# Mic_SPK2.net
KiCad netlist of a schematic drawn in Altium Designer
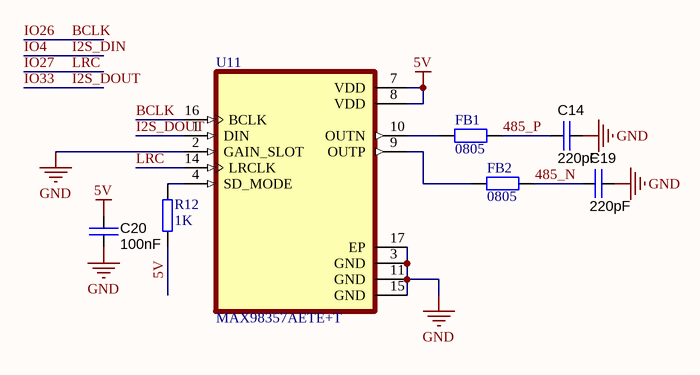
[diagram p0: Mic_SPK2.SchDoc]

(export (version "E")
  (design (tool "Eeschema 10.0.6"))
  (components
    (comp (ref "C14")
      (value "220pF")
      (footprint "CAPC1608X90N")
      (description "Capacitor SMD Cer 470nF 10% 16V X7R 0603")
      (fields (field (name "TOLERANCE") "±10%"))
      (libsource (lib "My library altium") (part "CAP C_0603"))
    )
    (comp (ref "C19")
      (value "220pF")
      (footprint "CAPC1608X90N")
      (description "Capacitor SMD Cer 470nF 10% 16V X7R 0603")
      (fields (field (name "TOLERANCE") "±10%"))
      (libsource (lib "My library altium") (part "CAP C_0603"))
    )
    (comp (ref "C20")
      (value "100nF")
      (footprint "CAPC1608X90N")
      (description "Capacitor SMD Cer 470nF 10% 16V X7R 0603")
      (fields (field (name "TOLERANCE") "±10%"))
      (libsource (lib "My library altium") (part "CAP C_0603"))
    )
    (comp (ref "FB1")
      (value "0805")
      (footprint "DIEN TRO 0805")
      (description "Resistor SMD 0805")
      (fields (field (name "Comment") "R0805") (field (name "PUBLISHER") "Altium Limited"))
      (libsource (lib "My Library") (part "R0805"))
    )
    (comp (ref "FB2")
      (value "0805")
      (footprint "DIEN TRO 0805")
      (description "Resistor SMD 0805")
      (fields (field (name "Comment") "R0805") (field (name "PUBLISHER") "Altium Limited"))
      (libsource (lib "My Library") (part "R0805"))
    )
    (comp (ref "R12")
      (value "1K")
      (footprint "SMT0603")
      (description "RES SM 0603 1K")
      (fields (field (name "Comment") "Resistor"))
      (libsource (lib "electronpowered") (part "RES-SM-0603-1K"))
    )
    (comp (ref "U11")
      (value "MAX98357AETE+T")
      (footprint "QFN50P300X300X80-17N")
      (description "Amplifier IC 1-Channel _Mono_ Class D 16-TQFN _3x3_")
      (fields (field (name "MF") "Maxim Integrated"))
      (libsource (lib "MAX98357AETE_T") (part "MAX98357AETE+T"))
    )
  )
  (nets
    (net (code "1") (name "/485_N") (class "Default")
      (node (ref "C19") (pin "1") (pintype "passive"))
      (node (ref "FB2") (pin "2") (pinfunction "2_2") (pintype "passive"))
    )
    (net (code "2") (name "/485_P") (class "Default")
      (node (ref "C14") (pin "1") (pintype "passive"))
      (node (ref "FB1") (pin "2") (pinfunction "2_2") (pintype "passive"))
    )
    (net (code "3") (name "/BCLK") (class "Default")
      (node (ref "U11") (pin "16") (pinfunction "BCLK_16") (pintype "input"))
    )
    (net (code "5") (name "/I2S_DOUT") (class "Default")
      (node (ref "U11") (pin "1") (pinfunction "DIN_1") (pintype "input"))
    )
    (net (code "6") (name "/IO27") (class "Default")
      (node (ref "U11") (pin "14") (pinfunction "LRCLK_14") (pintype "input"))
    )
    (net (code "7") (name "5V") (class "Default")
      (node (ref "C20") (pin "1") (pintype "passive"))
      (node (ref "R12") (pin "1") (pinfunction "1_1") (pintype "passive"))
      (node (ref "U11") (pin "7") (pinfunction "VDD_7") (pintype "power_in"))
      (node (ref "U11") (pin "8") (pinfunction "VDD_8") (pintype "power_in"))
    )
    (net (code "8") (name "GND") (class "Default")
      (node (ref "C14") (pin "2") (pintype "passive"))
      (node (ref "C19") (pin "2") (pintype "passive"))
      (node (ref "C20") (pin "2") (pintype "passive"))
      (node (ref "U11") (pin "11") (pinfunction "GND_11") (pintype "power_in"))
      (node (ref "U11") (pin "15") (pinfunction "GND_15") (pintype "power_in"))
      (node (ref "U11") (pin "17") (pinfunction "EP_17") (pintype "power_in"))
      (node (ref "U11") (pin "2") (pinfunction "GAIN_SLOT_2") (pintype "input"))
      (node (ref "U11") (pin "3") (pinfunction "GND_3") (pintype "power_in"))
    )
    (net (code "9") (name "Net-(U11-OUTN)") (class "Default")
      (node (ref "FB1") (pin "1") (pinfunction "1_1") (pintype "passive"))
      (node (ref "U11") (pin "10") (pinfunction "OUTN_10") (pintype "output"))
    )
    (net (code "10") (name "Net-(U11-OUTP)") (class "Default")
      (node (ref "FB2") (pin "1") (pinfunction "1_1") (pintype "passive"))
      (node (ref "U11") (pin "9") (pinfunction "OUTP_9") (pintype "output"))
    )
    (net (code "11") (name "Net-(U11-SD_MODE)") (class "Default")
      (node (ref "R12") (pin "2") (pinfunction "2_2") (pintype "passive"))
      (node (ref "U11") (pin "4") (pinfunction "SD_MODE_4") (pintype "input"))
    )
  )
)
